# ThermoE.net
KiCad netlist of a schematic drawn in Altium Designer
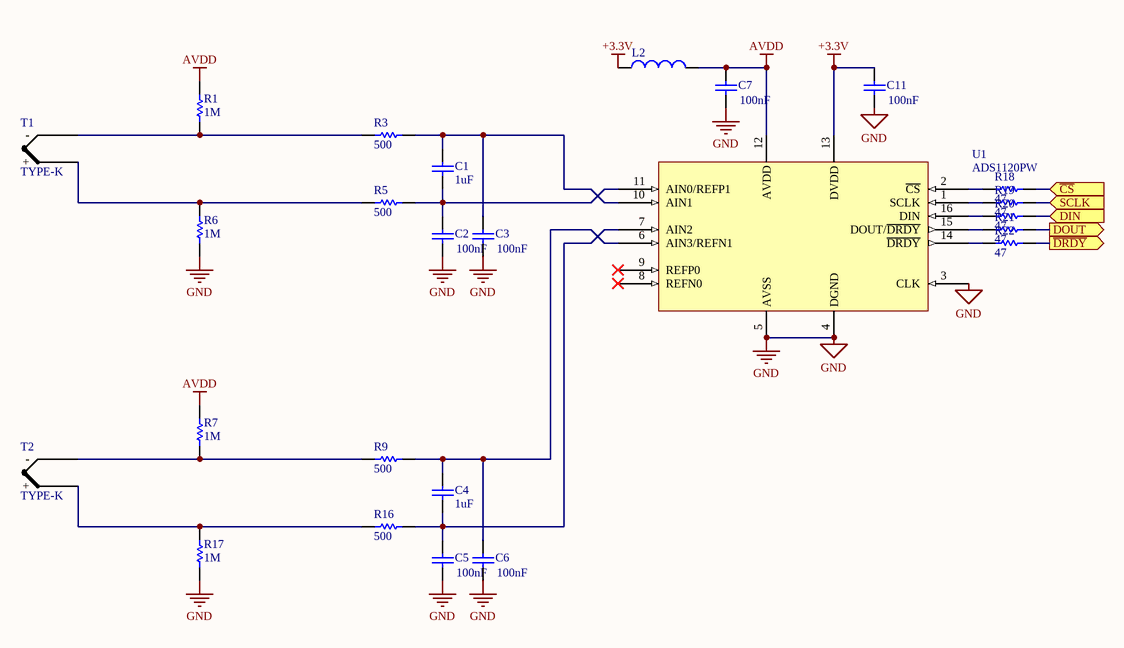
[diagram p0: ThermoE.SchDoc]

(export (version "E")
  (design (tool "Eeschema 10.0.6"))
  (components
    (comp (ref "C1")
      (value "1uF")
      (footprint "c603")
      (description "Capacitor")
      (fields (field (name "DESIGNER") "Parsa Malekpour"))
      (libsource (lib "ParsaLibrary") (part "Cap"))
    )
    (comp (ref "C2")
      (value "100nF")
      (footprint "c603")
      (description "Capacitor")
      (fields (field (name "DESIGNER") "Parsa Malekpour"))
      (libsource (lib "ParsaLibrary") (part "Cap"))
    )
    (comp (ref "C3")
      (value "100nF")
      (footprint "c603")
      (description "Capacitor")
      (fields (field (name "DESIGNER") "Parsa Malekpour"))
      (libsource (lib "ParsaLibrary") (part "Cap"))
    )
    (comp (ref "C4")
      (value "1uF")
      (footprint "c603")
      (description "Capacitor")
      (fields (field (name "DESIGNER") "Parsa Malekpour"))
      (libsource (lib "ParsaLibrary") (part "Cap"))
    )
    (comp (ref "C5")
      (value "100nF")
      (footprint "c603")
      (description "Capacitor")
      (fields (field (name "DESIGNER") "Parsa Malekpour"))
      (libsource (lib "ParsaLibrary") (part "Cap"))
    )
    (comp (ref "C6")
      (value "100nF")
      (footprint "c603")
      (description "Capacitor")
      (fields (field (name "DESIGNER") "Parsa Malekpour"))
      (libsource (lib "ParsaLibrary") (part "Cap"))
    )
    (comp (ref "C7")
      (value "100nF")
      (footprint "C603")
      (description "Capacitor")
      (fields (field (name "DESIGNER") "Parsa Malekpour"))
      (libsource (lib "ParsaLibrary") (part "Cap"))
    )
    (comp (ref "C11")
      (value "100nF")
      (footprint "C603")
      (description "Capacitor")
      (fields (field (name "DESIGNER") "Parsa Malekpour"))
      (libsource (lib "ParsaLibrary") (part "Cap"))
    )
    (comp (ref "L2")
      (value "1K")
      (footprint "r805")
      (description "FERRITE BEAD")
      (fields (field (name "PUBLISHER") "Altium Limited"))
      (libsource (lib "ParsaLibrary") (part "Ferrite Bead"))
    )
    (comp (ref "R1")
      (value "1M")
      (footprint "R0603")
      (description "Resistor")
      (fields (field (name "DESIGNER") "Parsa Malekpour"))
      (libsource (lib "ParsaLibrary") (part "Resistor"))
    )
    (comp (ref "R3")
      (value "500")
      (footprint "R0603")
      (description "Resistor")
      (fields (field (name "DESIGNER") "Parsa Malekpour"))
      (libsource (lib "ParsaLibrary") (part "Resistor"))
    )
    (comp (ref "R5")
      (value "500")
      (footprint "R0603")
      (description "Resistor")
      (fields (field (name "DESIGNER") "Parsa Malekpour"))
      (libsource (lib "ParsaLibrary") (part "Resistor"))
    )
    (comp (ref "R6")
      (value "1M")
      (footprint "R0603")
      (description "Resistor")
      (fields (field (name "DESIGNER") "Parsa Malekpour"))
      (libsource (lib "ParsaLibrary") (part "Resistor"))
    )
    (comp (ref "R7")
      (value "1M")
      (footprint "R0603")
      (description "Resistor")
      (fields (field (name "DESIGNER") "Parsa Malekpour"))
      (libsource (lib "ParsaLibrary") (part "Resistor"))
    )
    (comp (ref "R9")
      (value "500")
      (footprint "R0603")
      (description "Resistor")
      (fields (field (name "DESIGNER") "Parsa Malekpour"))
      (libsource (lib "ParsaLibrary") (part "Resistor"))
    )
    (comp (ref "R16")
      (value "500")
      (footprint "R0603")
      (description "Resistor")
      (fields (field (name "DESIGNER") "Parsa Malekpour"))
      (libsource (lib "ParsaLibrary") (part "Resistor"))
    )
    (comp (ref "R17")
      (value "1M")
      (footprint "R0603")
      (description "Resistor")
      (fields (field (name "DESIGNER") "Parsa Malekpour"))
      (libsource (lib "ParsaLibrary") (part "Resistor"))
    )
    (comp (ref "R18")
      (value "47")
      (footprint "R0603")
      (description "Resistor")
      (fields (field (name "DESIGNER") "Parsa Malekpour"))
      (libsource (lib "ParsaLibrary") (part "Resistor"))
    )
    (comp (ref "R19")
      (value "47")
      (footprint "R0603")
      (description "Resistor")
      (fields (field (name "DESIGNER") "Parsa Malekpour"))
      (libsource (lib "ParsaLibrary") (part "Resistor"))
    )
    (comp (ref "R20")
      (value "47")
      (footprint "R0603")
      (description "Resistor")
      (fields (field (name "DESIGNER") "Parsa Malekpour"))
      (libsource (lib "ParsaLibrary") (part "Resistor"))
    )
    (comp (ref "R21")
      (value "47")
      (footprint "R0603")
      (description "Resistor")
      (fields (field (name "DESIGNER") "Parsa Malekpour"))
      (libsource (lib "ParsaLibrary") (part "Resistor"))
    )
    (comp (ref "R22")
      (value "47")
      (footprint "R0603")
      (description "Resistor")
      (fields (field (name "DESIGNER") "Parsa Malekpour"))
      (libsource (lib "ParsaLibrary") (part "Resistor"))
    )
    (comp (ref "T1")
      (value "TYPE-K")
      (footprint "PCC-SMP")
      (libsource (lib "ParsaLibrary") (part "THERMOCOUPLE"))
    )
    (comp (ref "T2")
      (value "TYPE-K")
      (footprint "PCC-SMP")
      (libsource (lib "ParsaLibrary") (part "THERMOCOUPLE"))
    )
    (comp (ref "U1")
      (value "ADS1120PW")
      (footprint "TSSOP-16")
      (description "ADS1120 4-Channel, 2-kSPS, Low-Power, 16-Bit ADC with Integrated PGA and Reference")
      (libsource (lib "ParsaLibrary") (part "ADS1120PW"))
    )
  )
  (nets
    (net (code "1") (name "+3.3V") (class "Default")
      (node (ref "C11") (pin "2") (pinfunction "2_2") (pintype "passive"))
      (node (ref "L2") (pin "1") (pinfunction "1_1") (pintype "passive"))
      (node (ref "U1") (pin "13") (pinfunction "DVDD_13") (pintype "power_in"))
    )
    (net (code "2") (name "/DIN") (class "Default")
      (node (ref "R20") (pin "1") (pinfunction "1_1") (pintype "passive"))
    )
    (net (code "3") (name "/DOUT") (class "Default")
      (node (ref "R21") (pin "1") (pinfunction "1_1") (pintype "passive"))
    )
    (net (code "4") (name "/SCLK") (class "Default")
      (node (ref "R19") (pin "1") (pinfunction "1_1") (pintype "passive"))
    )
    (net (code "5") (name "/~{CS}") (class "Default")
      (node (ref "R18") (pin "1") (pinfunction "1_1") (pintype "passive"))
    )
    (net (code "6") (name "/~{DRDY}") (class "Default")
      (node (ref "R22") (pin "1") (pinfunction "1_1") (pintype "passive"))
    )
    (net (code "7") (name "AVDD") (class "Default")
      (node (ref "C7") (pin "2") (pinfunction "2_2") (pintype "passive"))
      (node (ref "L2") (pin "2") (pinfunction "2_2") (pintype "passive"))
      (node (ref "R1") (pin "2") (pinfunction "2_2") (pintype "passive"))
      (node (ref "R7") (pin "2") (pinfunction "2_2") (pintype "passive"))
      (node (ref "U1") (pin "12") (pinfunction "AVDD_12") (pintype "power_in"))
    )
    (net (code "8") (name "GND") (class "Default")
      (node (ref "C11") (pin "1") (pinfunction "1_1") (pintype "passive"))
      (node (ref "C2") (pin "1") (pinfunction "1_1") (pintype "passive"))
      (node (ref "C3") (pin "1") (pinfunction "1_1") (pintype "passive"))
      (node (ref "C5") (pin "1") (pinfunction "1_1") (pintype "passive"))
      (node (ref "C6") (pin "1") (pinfunction "1_1") (pintype "passive"))
      (node (ref "C7") (pin "1") (pinfunction "1_1") (pintype "passive"))
      (node (ref "R17") (pin "1") (pinfunction "1_1") (pintype "passive"))
      (node (ref "R6") (pin "1") (pinfunction "1_1") (pintype "passive"))
      (node (ref "U1") (pin "3") (pinfunction "CLK_3") (pintype "input"))
      (node (ref "U1") (pin "4") (pinfunction "DGND_4") (pintype "power_in"))
      (node (ref "U1") (pin "5") (pinfunction "AVSS_5") (pintype "power_in"))
    )
    (net (code "9") (name "Net-(T1-+)") (class "Default")
      (node (ref "R5") (pin "2") (pinfunction "2_2") (pintype "passive"))
      (node (ref "R6") (pin "2") (pinfunction "2_2") (pintype "passive"))
      (node (ref "T1") (pin "2") (pinfunction "+_2") (pintype "passive"))
    )
    (net (code "10") (name "Net-(T1--)") (class "Default")
      (node (ref "R1") (pin "1") (pinfunction "1_1") (pintype "passive"))
      (node (ref "R3") (pin "2") (pinfunction "2_2") (pintype "passive"))
      (node (ref "T1") (pin "1") (pinfunction "-_1") (pintype "passive"))
    )
    (net (code "11") (name "Net-(T2-+)") (class "Default")
      (node (ref "R16") (pin "2") (pinfunction "2_2") (pintype "passive"))
      (node (ref "R17") (pin "2") (pinfunction "2_2") (pintype "passive"))
      (node (ref "T2") (pin "2") (pinfunction "+_2") (pintype "passive"))
    )
    (net (code "12") (name "Net-(T2--)") (class "Default")
      (node (ref "R7") (pin "1") (pinfunction "1_1") (pintype "passive"))
      (node (ref "R9") (pin "2") (pinfunction "2_2") (pintype "passive"))
      (node (ref "T2") (pin "1") (pinfunction "-_1") (pintype "passive"))
    )
    (net (code "13") (name "Net-(U1-AIN0{slash}REFP1)") (class "Default")
      (node (ref "C1") (pin "1") (pinfunction "1_1") (pintype "passive"))
      (node (ref "C2") (pin "2") (pinfunction "2_2") (pintype "passive"))
      (node (ref "R5") (pin "1") (pinfunction "1_1") (pintype "passive"))
      (node (ref "U1") (pin "11") (pinfunction "AIN0/REFP1_11") (pintype "input"))
    )
    (net (code "14") (name "Net-(U1-AIN1)") (class "Default")
      (node (ref "C1") (pin "2") (pinfunction "2_2") (pintype "passive"))
      (node (ref "C3") (pin "2") (pinfunction "2_2") (pintype "passive"))
      (node (ref "R3") (pin "1") (pinfunction "1_1") (pintype "passive"))
      (node (ref "U1") (pin "10") (pinfunction "AIN1_10") (pintype "input"))
    )
    (net (code "15") (name "Net-(U1-AIN2)") (class "Default")
      (node (ref "C4") (pin "1") (pinfunction "1_1") (pintype "passive"))
      (node (ref "C5") (pin "2") (pinfunction "2_2") (pintype "passive"))
      (node (ref "R16") (pin "1") (pinfunction "1_1") (pintype "passive"))
      (node (ref "U1") (pin "7") (pinfunction "AIN2_7") (pintype "input"))
    )
    (net (code "16") (name "Net-(U1-AIN3{slash}REFN1)") (class "Default")
      (node (ref "C4") (pin "2") (pinfunction "2_2") (pintype "passive"))
      (node (ref "C6") (pin "2") (pinfunction "2_2") (pintype "passive"))
      (node (ref "R9") (pin "1") (pinfunction "1_1") (pintype "passive"))
      (node (ref "U1") (pin "6") (pinfunction "AIN3/REFN1_6") (pintype "input"))
    )
    (net (code "17") (name "Net-(U1-DIN)") (class "Default")
      (node (ref "R20") (pin "2") (pinfunction "2_2") (pintype "passive"))
      (node (ref "U1") (pin "16") (pinfunction "DIN_16") (pintype "input"))
    )
    (net (code "18") (name "Net-(U1-DOUT{slash}~{DRDY})") (class "Default")
      (node (ref "R21") (pin "2") (pinfunction "2_2") (pintype "passive"))
      (node (ref "U1") (pin "15") (pinfunction "DOUT/~{DRDY}_15") (pintype "output"))
    )
    (net (code "19") (name "Net-(U1-SCLK)") (class "Default")
      (node (ref "R19") (pin "2") (pinfunction "2_2") (pintype "passive"))
      (node (ref "U1") (pin "1") (pinfunction "SCLK_1") (pintype "input"))
    )
    (net (code "20") (name "Net-(U1-~{CS})") (class "Default")
      (node (ref "R18") (pin "2") (pinfunction "2_2") (pintype "passive"))
      (node (ref "U1") (pin "2") (pinfunction "~{CS}_2") (pintype "input"))
    )
    (net (code "21") (name "Net-(U1-~{DRDY})") (class "Default")
      (node (ref "R22") (pin "2") (pinfunction "2_2") (pintype "passive"))
      (node (ref "U1") (pin "14") (pinfunction "~{DRDY}_14") (pintype "output"))
    )
    (net (code "22") (name "unconnected-(U1-REFN0-Pad8)") (class "Default")
      (node (ref "U1") (pin "8") (pinfunction "REFN0_8") (pintype "input+no_connect"))
    )
    (net (code "23") (name "unconnected-(U1-REFP0-Pad9)") (class "Default")
      (node (ref "U1") (pin "9") (pinfunction "REFP0_9") (pintype "input+no_connect"))
    )
  )
)
